# STM32_SIM800.net
KiCad netlist of a schematic drawn in Altium Designer
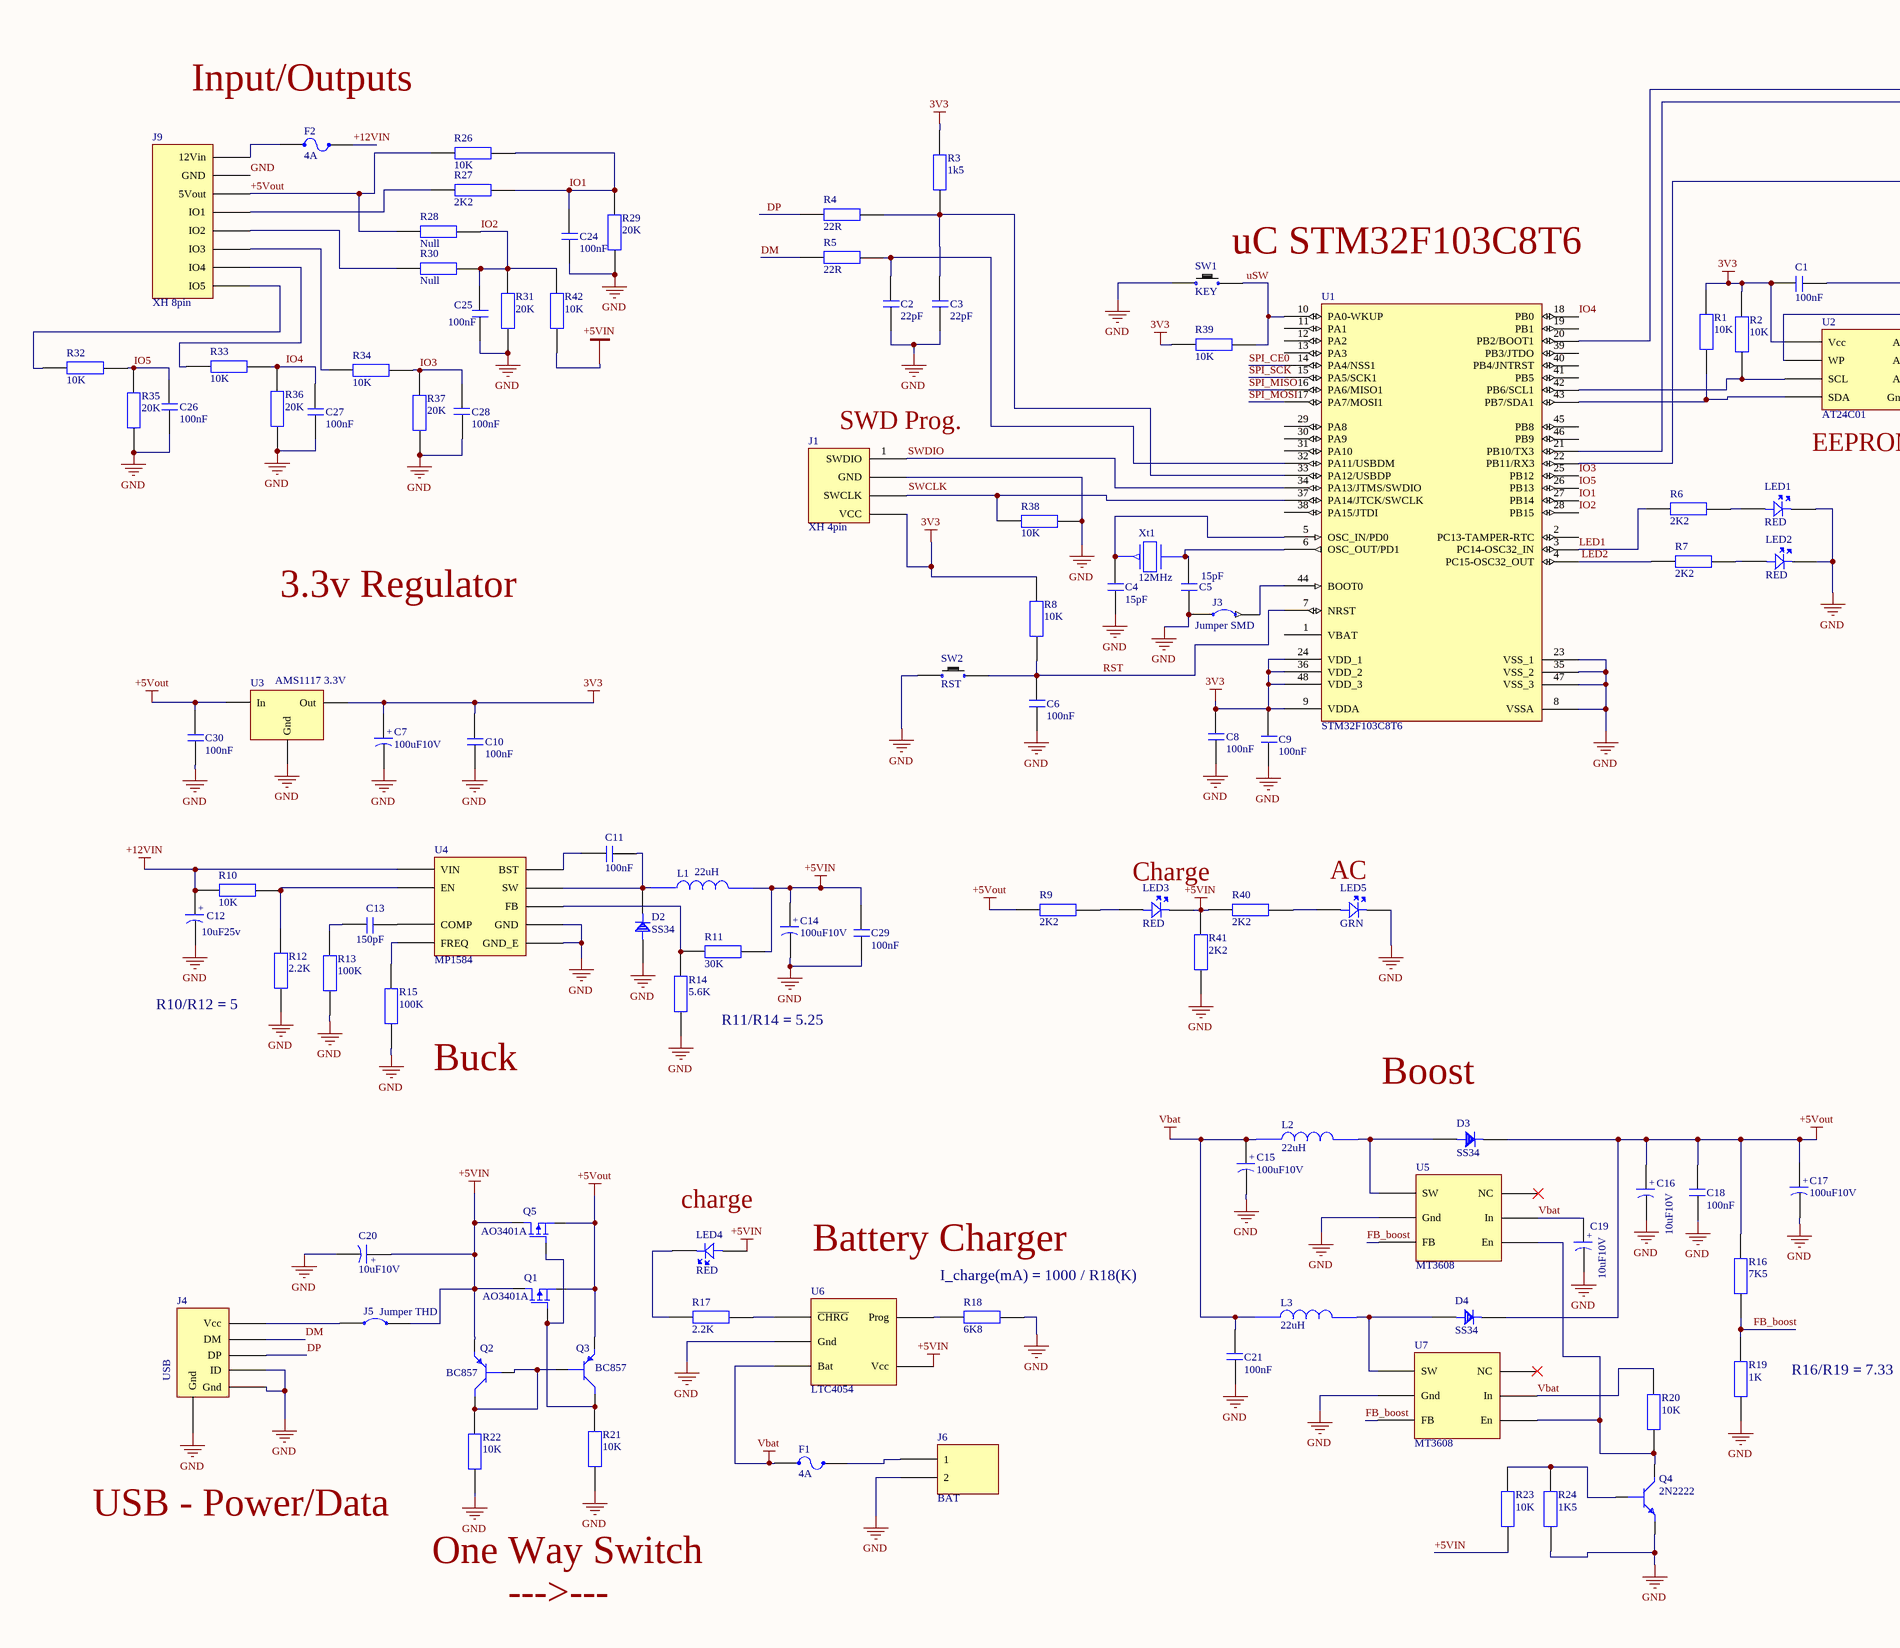
[diagram p0: STM32_SIM800.SchDoc, left]
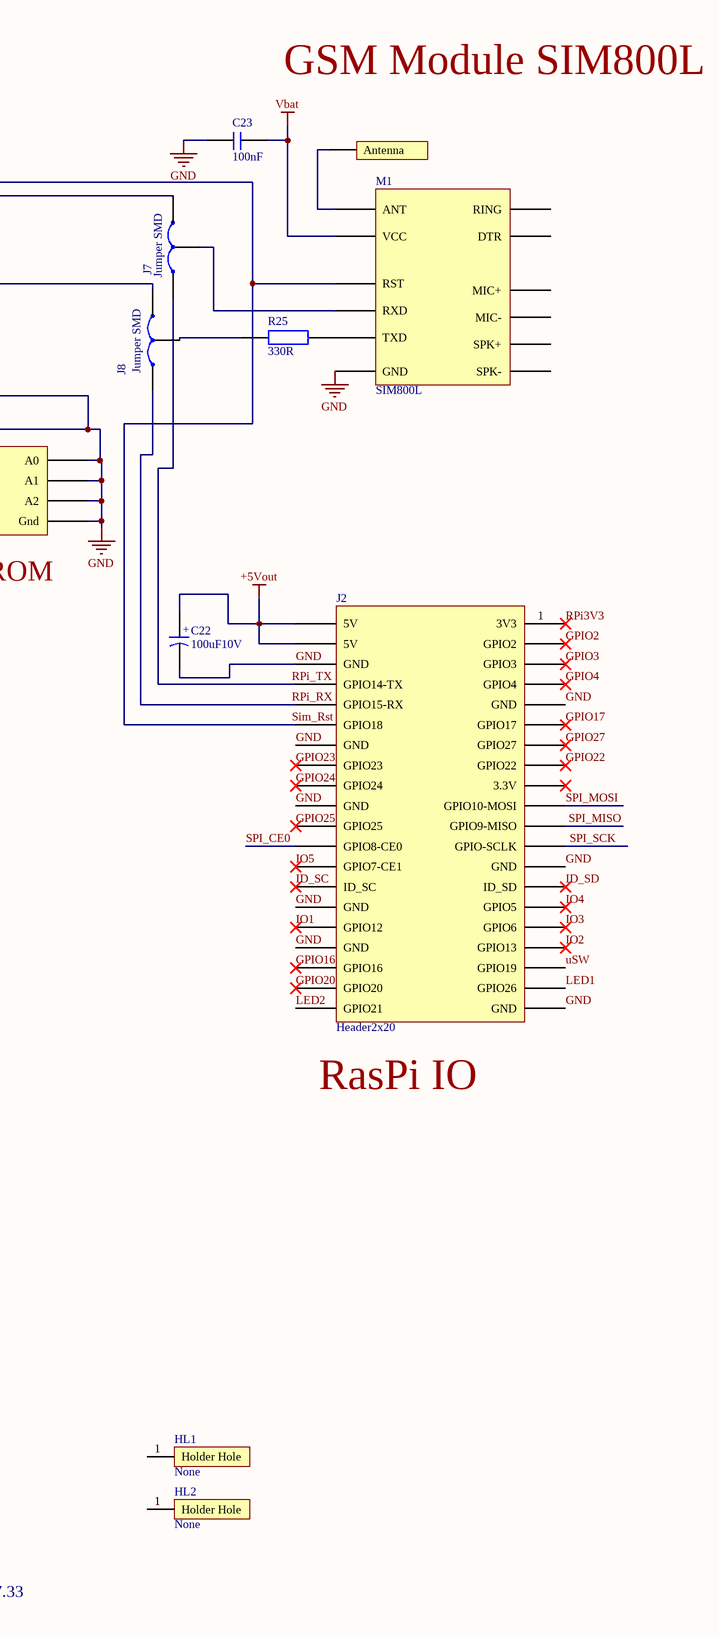
[diagram p1: STM32_SIM800.SchDoc, right]

(export (version "E")
  (design (tool "Eeschema 10.0.6"))
  (components
    (comp (ref "C1")
      (value "100nF")
      (footprint "CAP_0805")
      (description "Capacitor SMD 0805")
      (libsource (lib "My_Integrated_Library") (part "Cap0805"))
    )
    (comp (ref "C2")
      (value "22pF")
      (footprint "CAP_0805")
      (description "Capacitor SMD 0805")
      (libsource (lib "My_Integrated_Library") (part "Cap0805"))
    )
    (comp (ref "C3")
      (value "22pF")
      (footprint "CAP_0805")
      (description "Capacitor SMD 0805")
      (libsource (lib "My_Integrated_Library") (part "Cap0805"))
    )
    (comp (ref "C4")
      (value "15pF")
      (footprint "CAP_0805")
      (description "Capacitor SMD 0805")
      (libsource (lib "My_Integrated_Library") (part "Cap0805"))
    )
    (comp (ref "C5")
      (value "15pF")
      (footprint "CAP_0805")
      (description "Capacitor SMD 0805")
      (libsource (lib "My_Integrated_Library") (part "Cap0805"))
    )
    (comp (ref "C6")
      (value "100nF")
      (footprint "CAP_0805")
      (description "Capacitor SMD 0805")
      (libsource (lib "My_Integrated_Library") (part "Cap0805"))
    )
    (comp (ref "C7")
      (value "100uF10V")
      (footprint "Cap_Tan_Size_B")
      (description "Capacitor SMD Tantalium Size B")
      (libsource (lib "My_Integrated_Library") (part "Cap_Tant_B"))
    )
    (comp (ref "C8")
      (value "100nF")
      (footprint "CAP_0805")
      (description "Capacitor SMD 0805")
      (libsource (lib "My_Integrated_Library") (part "Cap0805"))
    )
    (comp (ref "C9")
      (value "100nF")
      (footprint "CAP_0805")
      (description "Capacitor SMD 0805")
      (libsource (lib "My_Integrated_Library") (part "Cap0805"))
    )
    (comp (ref "C10")
      (value "100nF")
      (footprint "CAP_0805")
      (description "Capacitor SMD 0805")
      (libsource (lib "My_Integrated_Library") (part "Cap0805"))
    )
    (comp (ref "C11")
      (value "100nF")
      (footprint "CAP_0805")
      (description "Capacitor SMD 0805")
      (libsource (lib "My_Integrated_Library") (part "Cap0805"))
    )
    (comp (ref "C12")
      (value "10uF25v")
      (footprint "Cap_Tan_Size_B")
      (description "Capacitor SMD Tantalium Size B")
      (libsource (lib "My_Integrated_Library") (part "Cap_Tant_B"))
    )
    (comp (ref "C13")
      (value "150pF")
      (footprint "CAP_0805")
      (description "Capacitor SMD 0805")
      (libsource (lib "My_Integrated_Library") (part "Cap0805"))
    )
    (comp (ref "C14")
      (value "100uF10V")
      (footprint "Cap_Tan_Size_B")
      (description "Capacitor SMD Tantalium Size B")
      (libsource (lib "My_Integrated_Library") (part "Cap_Tant_B"))
    )
    (comp (ref "C15")
      (value "100uF10V")
      (footprint "Cap_Tan_Size_B")
      (description "Capacitor SMD Tantalium Size B")
      (libsource (lib "My_Integrated_Library") (part "Cap_Tant_B"))
    )
    (comp (ref "C16")
      (value "10uF10V")
      (footprint "Cap_Tan_Size_B")
      (description "Capacitor SMD Tantalium Size B")
      (libsource (lib "My_Integrated_Library") (part "Cap_Tant_B"))
    )
    (comp (ref "C17")
      (value "100uF10V")
      (footprint "Cap_Tan_Size_B")
      (description "Capacitor SMD Tantalium Size B")
      (libsource (lib "My_Integrated_Library") (part "Cap_Tant_B"))
    )
    (comp (ref "C18")
      (value "100nF")
      (footprint "CAP_0805")
      (description "Capacitor SMD 0805")
      (libsource (lib "My_Integrated_Library") (part "Cap0805"))
    )
    (comp (ref "C19")
      (value "10uF10V")
      (footprint "Cap_Tan_Size_B")
      (description "Capacitor SMD Tantalium Size B")
      (libsource (lib "My_Integrated_Library") (part "Cap_Tant_B"))
    )
    (comp (ref "C20")
      (value "10uF10V")
      (footprint "Cap_Tan_Size_B")
      (description "Capacitor SMD Tantalium Size B")
      (libsource (lib "My_Integrated_Library") (part "Cap_Tant_B"))
    )
    (comp (ref "C21")
      (value "100nF")
      (footprint "CAP_0805")
      (description "Capacitor SMD 0805")
      (libsource (lib "My_Integrated_Library") (part "Cap0805"))
    )
    (comp (ref "C22")
      (value "100uF10V")
      (footprint "Cap_Tan_Size_B")
      (description "Capacitor SMD Tantalium Size B")
      (libsource (lib "My_Integrated_Library") (part "Cap_Tant_B"))
    )
    (comp (ref "C23")
      (value "100nF")
      (footprint "CAP_0805")
      (description "Capacitor SMD 0805")
      (libsource (lib "My_Integrated_Library") (part "Cap0805"))
    )
    (comp (ref "C24")
      (value "100nF")
      (footprint "CAP_0805")
      (description "Capacitor SMD 0805")
      (libsource (lib "My_Integrated_Library") (part "Cap0805"))
    )
    (comp (ref "C25")
      (value "100nF")
      (footprint "CAP_0805")
      (description "Capacitor SMD 0805")
      (libsource (lib "My_Integrated_Library") (part "Cap0805"))
    )
    (comp (ref "C26")
      (value "100nF")
      (footprint "CAP_0805")
      (description "Capacitor SMD 0805")
      (libsource (lib "My_Integrated_Library") (part "Cap0805"))
    )
    (comp (ref "C27")
      (value "100nF")
      (footprint "CAP_0805")
      (description "Capacitor SMD 0805")
      (libsource (lib "My_Integrated_Library") (part "Cap0805"))
    )
    (comp (ref "C28")
      (value "100nF")
      (footprint "CAP_0805")
      (description "Capacitor SMD 0805")
      (libsource (lib "My_Integrated_Library") (part "Cap0805"))
    )
    (comp (ref "C29")
      (value "100nF")
      (footprint "CAP_0805")
      (description "Capacitor SMD 0805")
      (libsource (lib "My_Integrated_Library") (part "Cap0805"))
    )
    (comp (ref "C30")
      (value "100nF")
      (footprint "CAP_0805")
      (description "Capacitor SMD 0805")
      (libsource (lib "My_Integrated_Library") (part "Cap0805"))
    )
    (comp (ref "D2")
      (value "SS34")
      (footprint "Diode_SMA")
      (description "Diode SMD Shotkey 1N5822 SS34")
      (libsource (lib "My_Integrated_Library") (part "Diode_SMA"))
    )
    (comp (ref "D3")
      (value "SS34")
      (footprint "Diode_SMA")
      (description "Diode SMD Shotkey 1N5822 SS34")
      (libsource (lib "My_Integrated_Library") (part "Diode_SMA"))
    )
    (comp (ref "D4")
      (value "SS34")
      (footprint "Diode_SMA")
      (description "Diode SMD Shotkey 1N5822 SS34")
      (libsource (lib "My_Integrated_Library") (part "Diode_SMA"))
    )
    (comp (ref "F1")
      (value "4A")
      (footprint "fuse_1206")
      (description "Fuse SMD 1206")
      (libsource (lib "My_Integrated_Library") (part "Fuse1206"))
    )
    (comp (ref "F2")
      (value "4A")
      (footprint "fuse_1206")
      (description "Fuse SMD 1206")
      (libsource (lib "My_Integrated_Library") (part "Fuse1206"))
    )
    (comp (ref "HL1")
      (value "None")
      (footprint "Holder_hole")
      (description "PCB Holder Hole")
      (libsource (lib "My_Integrated_Library") (part "Holder_Hole"))
    )
    (comp (ref "HL2")
      (value "None")
      (footprint "Holder_hole")
      (description "PCB Holder Hole")
      (libsource (lib "My_Integrated_Library") (part "Holder_Hole"))
    )
    (comp (ref "J1")
      (value "XH 4pin")
      (footprint "XH-4pin")
      (description "Connector XH Female 4-pin")
      (libsource (lib "My_Integrated_Library") (part "Con_XH_4pin"))
    )
    (comp (ref "J2")
      (value "Header2x20")
      (footprint "Header_2x20_female")
      (description "Pin Header 2x20 pitch=2.54mm")
      (libsource (lib "My_Integrated_Library") (part "Header2x20"))
    )
    (comp (ref "J3")
      (value "Jumper SMD")
      (footprint "Jumper_smd")
      (libsource (lib "My_Integrated_Library") (part "Jump_smd"))
    )
    (comp (ref "J4")
      (value "USB")
      (footprint "Micro_USB_smd")
      (description "Micro USB Female connector SMD")
      (libsource (lib "My_Integrated_Library") (part "MicroUSB_SMD"))
    )
    (comp (ref "J5")
      (value "Jumper THD")
      (footprint "Jumper_2pin")
      (description "Jumper pin header + jumper 2pin pirch=2.54mm")
      (libsource (lib "My_Integrated_Library") (part "Jumper DIP"))
    )
    (comp (ref "J6")
      (value "BAT")
      (footprint "XH-2pin")
      (description "Connector XH Female 2-pin")
      (libsource (lib "My_Integrated_Library") (part "Con_XH_2pin"))
    )
    (comp (ref "J7")
      (value "Jumper SMD")
      (footprint "Jumper_smd_3pin")
      (libsource (lib "My_Integrated_Library") (part "Jump_smd_3tap"))
    )
    (comp (ref "J8")
      (value "Jumper SMD")
      (footprint "Jumper_smd_3pin")
      (libsource (lib "My_Integrated_Library") (part "Jump_smd_3tap"))
    )
    (comp (ref "J9")
      (value "XH 8pin")
      (footprint "XH-8pin - RA")
      (description "Connector XH Female 8-pin")
      (libsource (lib "My_Integrated_Library") (part "Con_XH_8pin"))
    )
    (comp (ref "L1")
      (value "22uH")
      (footprint "L_10x10")
      (description "SMD Power Inductor 10X10mm")
      (libsource (lib "My_Integrated_Library") (part "Inductor_10x10"))
    )
    (comp (ref "L2")
      (value "22uH")
      (footprint "L_10x10")
      (description "SMD Power Inductor 10X10mm")
      (libsource (lib "My_Integrated_Library") (part "Inductor_10x10"))
    )
    (comp (ref "L3")
      (value "22uH")
      (footprint "L_10x10")
      (description "SMD Power Inductor 10X10mm")
      (libsource (lib "My_Integrated_Library") (part "Inductor_10x10"))
    )
    (comp (ref "LED1")
      (value "RED")
      (footprint "LED_0805_Red")
      (description "LED SMD 0805 Red")
      (libsource (lib "My_Integrated_Library") (part "LED_0805_Red"))
    )
    (comp (ref "LED2")
      (value "RED")
      (footprint "LED_0805_Red")
      (description "LED SMD 0805 Red")
      (libsource (lib "My_Integrated_Library") (part "LED_0805_Red"))
    )
    (comp (ref "LED3")
      (value "RED")
      (footprint "LED_0805_Red")
      (description "LED SMD 0805 Red")
      (libsource (lib "My_Integrated_Library") (part "LED_0805_Red"))
    )
    (comp (ref "LED4")
      (value "RED")
      (footprint "LED_0805_Red")
      (description "LED SMD 0805 Red")
      (libsource (lib "My_Integrated_Library") (part "LED_0805_Red"))
    )
    (comp (ref "LED5")
      (value "GRN")
      (footprint "LED_0805_Red")
      (description "LED SMD 0805 Red")
      (libsource (lib "My_Integrated_Library") (part "LED_0805_Red"))
    )
    (comp (ref "M1")
      (value "SIM800L")
      (footprint "SIM800L")
      (description "SIM800L GSM Module")
      (libsource (lib "My_Integrated_Library") (part "SIM800L"))
    )
    (comp (ref "Q1")
      (value "AO3401A")
      (footprint "SOT23 - P-Channel")
      (description "MOSFET P-Channel SMD SOT23")
      (libsource (lib "My_Integrated_Library") (part "Mosfet_P_SOT23"))
    )
    (comp (ref "Q2")
      (value "BC857")
      (footprint "SOT23-PNP")
      (description "PNP Transistor SMD SOT23")
      (libsource (lib "My_Integrated_Library") (part "BJT PNP SOT23"))
    )
    (comp (ref "Q3")
      (value "BC857")
      (footprint "SOT23-PNP")
      (description "PNP Transistor SMD SOT23")
      (libsource (lib "My_Integrated_Library") (part "BJT PNP SOT23"))
    )
    (comp (ref "Q4")
      (value "2N2222")
      (footprint "SOT23-NPN")
      (description "NPN Transistor SMD SOT23")
      (libsource (lib "My_Integrated_Library") (part "BJT_NPN_SOT23"))
    )
    (comp (ref "Q5")
      (value "AO3401A")
      (footprint "SOT23 - P-Channel")
      (description "MOSFET P-Channel SMD SOT23")
      (libsource (lib "My_Integrated_Library") (part "Mosfet_P_SOT23"))
    )
    (comp (ref "R1")
      (value "10K")
      (footprint "RES_0805")
      (description "Resistor SMD 0805")
      (libsource (lib "My_Integrated_Library") (part "Res0805"))
    )
    (comp (ref "R2")
      (value "10K")
      (footprint "RES_0805")
      (description "Resistor SMD 0805")
      (libsource (lib "My_Integrated_Library") (part "Res0805"))
    )
    (comp (ref "R3")
      (value "1k5")
      (footprint "RES_0805")
      (description "Resistor SMD 0805")
      (libsource (lib "My_Integrated_Library") (part "Res0805"))
    )
    (comp (ref "R4")
      (value "22R")
      (footprint "RES_0805")
      (description "Resistor SMD 0805")
      (libsource (lib "My_Integrated_Library") (part "Res0805"))
    )
    (comp (ref "R5")
      (value "22R")
      (footprint "RES_0805")
      (description "Resistor SMD 0805")
      (libsource (lib "My_Integrated_Library") (part "Res0805"))
    )
    (comp (ref "R6")
      (value "2K2")
      (footprint "RES_0805")
      (description "Resistor SMD 0805")
      (libsource (lib "My_Integrated_Library") (part "Res0805"))
    )
    (comp (ref "R7")
      (value "2K2")
      (footprint "RES_0805")
      (description "Resistor SMD 0805")
      (libsource (lib "My_Integrated_Library") (part "Res0805"))
    )
    (comp (ref "R8")
      (value "10K")
      (footprint "RES_0805")
      (description "Resistor SMD 0805")
      (libsource (lib "My_Integrated_Library") (part "Res0805"))
    )
    (comp (ref "R9")
      (value "2K2")
      (footprint "RES_0805")
      (description "Resistor SMD 0805")
      (libsource (lib "My_Integrated_Library") (part "Res0805"))
    )
    (comp (ref "R10")
      (value "10K")
      (footprint "RES_0805")
      (description "Resistor SMD 0805")
      (libsource (lib "My_Integrated_Library") (part "Res0805"))
    )
    (comp (ref "R11")
      (value "30K")
      (footprint "RES_0805")
      (description "Resistor SMD 0805")
      (libsource (lib "My_Integrated_Library") (part "Res0805"))
    )
    (comp (ref "R12")
      (value "2.2K")
      (footprint "RES_0805")
      (description "Resistor SMD 0805")
      (libsource (lib "My_Integrated_Library") (part "Res0805"))
    )
    (comp (ref "R13")
      (value "100K")
      (footprint "RES_0805")
      (description "Resistor SMD 0805")
      (libsource (lib "My_Integrated_Library") (part "Res0805"))
    )
    (comp (ref "R14")
      (value "5.6K")
      (footprint "RES_0805")
      (description "Resistor SMD 0805")
      (libsource (lib "My_Integrated_Library") (part "Res0805"))
    )
    (comp (ref "R15")
      (value "100K")
      (footprint "RES_0805")
      (description "Resistor SMD 0805")
      (libsource (lib "My_Integrated_Library") (part "Res0805"))
    )
    (comp (ref "R16")
      (value "7K5")
      (footprint "RES_0805")
      (description "Resistor SMD 0805")
      (libsource (lib "My_Integrated_Library") (part "Res0805"))
    )
    (comp (ref "R17")
      (value "2.2K")
      (footprint "RES_0805")
      (description "Resistor SMD 0805")
      (libsource (lib "My_Integrated_Library") (part "Res0805"))
    )
    (comp (ref "R18")
      (value "6K8")
      (footprint "RES_0805")
      (description "Resistor SMD 0805")
      (libsource (lib "My_Integrated_Library") (part "Res0805"))
    )
    (comp (ref "R19")
      (value "1K")
      (footprint "RES_0805")
      (description "Resistor SMD 0805")
      (libsource (lib "My_Integrated_Library") (part "Res0805"))
    )
    (comp (ref "R20")
      (value "10K")
      (footprint "RES_0805")
      (description "Resistor SMD 0805")
      (libsource (lib "My_Integrated_Library") (part "Res0805"))
    )
    (comp (ref "R21")
      (value "10K")
      (footprint "RES_0805")
      (description "Resistor SMD 0805")
      (libsource (lib "My_Integrated_Library") (part "Res0805"))
    )
    (comp (ref "R22")
      (value "10K")
      (footprint "RES_0805")
      (description "Resistor SMD 0805")
      (libsource (lib "My_Integrated_Library") (part "Res0805"))
    )
    (comp (ref "R23")
      (value "10K")
      (footprint "RES_0805")
      (description "Resistor SMD 0805")
      (libsource (lib "My_Integrated_Library") (part "Res0805"))
    )
    (comp (ref "R24")
      (value "1K5")
      (footprint "RES_0805")
      (description "Resistor SMD 0805")
      (libsource (lib "My_Integrated_Library") (part "Res0805"))
    )
    (comp (ref "R25")
      (value "330R")
      (footprint "RES_0805")
      (description "Resistor SMD 0805")
      (libsource (lib "My_Integrated_Library") (part "Res0805"))
    )
    (comp (ref "R26")
      (value "10K")
      (footprint "RES_0805")
      (description "Resistor SMD 0805")
      (libsource (lib "My_Integrated_Library") (part "Res0805"))
    )
    (comp (ref "R27")
      (value "2K2")
      (footprint "RES_0805")
      (description "Resistor SMD 0805")
      (libsource (lib "My_Integrated_Library") (part "Res0805"))
    )
    (comp (ref "R28")
      (value "Null")
      (footprint "RES_0805")
      (description "Resistor SMD 0805")
      (libsource (lib "My_Integrated_Library") (part "Res0805"))
    )
    (comp (ref "R29")
      (value "20K")
      (footprint "RES_0805")
      (description "Resistor SMD 0805")
      (libsource (lib "My_Integrated_Library") (part "Res0805"))
    )
    (comp (ref "R30")
      (value "Null")
      (footprint "RES_0805")
      (description "Resistor SMD 0805")
      (libsource (lib "My_Integrated_Library") (part "Res0805"))
    )
    (comp (ref "R31")
      (value "20K")
      (footprint "RES_0805")
      (description "Resistor SMD 0805")
      (libsource (lib "My_Integrated_Library") (part "Res0805"))
    )
    (comp (ref "R32")
      (value "10K")
      (footprint "RES_0805")
      (description "Resistor SMD 0805")
      (libsource (lib "My_Integrated_Library") (part "Res0805"))
    )
    (comp (ref "R33")
      (value "10K")
      (footprint "RES_0805")
      (description "Resistor SMD 0805")
      (libsource (lib "My_Integrated_Library") (part "Res0805"))
    )
    (comp (ref "R34")
      (value "10K")
      (footprint "RES_0805")
      (description "Resistor SMD 0805")
      (libsource (lib "My_Integrated_Library") (part "Res0805"))
    )
    (comp (ref "R35")
      (value "20K")
      (footprint "RES_0805")
      (description "Resistor SMD 0805")
      (libsource (lib "My_Integrated_Library") (part "Res0805"))
    )
    (comp (ref "R36")
      (value "20K")
      (footprint "RES_0805")
      (description "Resistor SMD 0805")
      (libsource (lib "My_Integrated_Library") (part "Res0805"))
    )
    (comp (ref "R37")
      (value "20K")
      (footprint "RES_0805")
      (description "Resistor SMD 0805")
      (libsource (lib "My_Integrated_Library") (part "Res0805"))
    )
    (comp (ref "R38")
      (value "10K")
      (footprint "RES_0805")
      (description "Resistor SMD 0805")
      (libsource (lib "My_Integrated_Library") (part "Res0805"))
    )
    (comp (ref "R39")
      (value "10K")
      (footprint "RES_0805")
      (description "Resistor SMD 0805")
      (libsource (lib "My_Integrated_Library") (part "Res0805"))
    )
    (comp (ref "R40")
      (value "2K2")
      (footprint "RES_0805")
      (description "Resistor SMD 0805")
      (libsource (lib "My_Integrated_Library") (part "Res0805"))
    )
    (comp (ref "R41")
      (value "2K2")
      (footprint "RES_0805")
      (description "Resistor SMD 0805")
      (libsource (lib "My_Integrated_Library") (part "Res0805"))
    )
    (comp (ref "R42")
      (value "10K")
      (footprint "RES_0805")
      (description "Resistor SMD 0805")
      (libsource (lib "My_Integrated_Library") (part "Res0805"))
    )
    (comp (ref "SW1")
      (value "KEY")
      (footprint "Tact_SW_SMD")
      (description "Tact switch SMD 2pin")
      (libsource (lib "My_Integrated_Library") (part "Tact_sw"))
    )
    (comp (ref "SW2")
      (value "RST")
      (footprint "Tact_SW_SMD")
      (description "Tact switch SMD 2pin")
      (libsource (lib "My_Integrated_Library") (part "Tact_sw"))
    )
    (comp (ref "TP1")
      (value "Ant.")
      (footprint "TP")
      (description "Test point")
      (libsource (lib "My_Integrated_Library") (part "TP"))
    )
    (comp (ref "U1")
      (value "STM32F103C8T6")
      (footprint "STM32F103C8-LQFP-48")
      (description "STM32 ARM-based 32-bit MCU with 64 Kbytes Flash, 48-pin LQFP, Industrial Temperature")
      (fields (field (name "PUBLISHER") "Altium Limited"))
      (libsource (lib "My_Integrated_Library") (part "STM32F103C8T6"))
    )
    (comp (ref "U2")
      (value "AT24C01")
      (footprint "AT24C01_SOP8")
      (description "AT24C01 EEPROM SMD SO8")
      (libsource (lib "My_Integrated_Library") (part "AT24C01"))
    )
    (comp (ref "U3")
      (value "AMS1117 3.3V")
      (footprint "AMS1117-SOT223")
      (description "AMS1117 Regulator 3.3V SMD SOT223")
      (libsource (lib "My_Integrated_Library") (part "AMS1117-SOT223"))
    )
    (comp (ref "U4")
      (value "MP1584")
      (footprint "MP1584-SOP8")
      (description "BUCK SMD SO8")
      (libsource (lib "My_Integrated_Library") (part "MP1584"))
    )
    (comp (ref "U5")
      (value "MT3608")
      (footprint "MT3608_SOT23-6")
      (description "Boost switching")
      (libsource (lib "My_Integrated_Library") (part "MT3608"))
    )
    (comp (ref "U6")
      (value "LTC4054")
      (footprint "LTC4054-4.2_SOT23-5")
      (description "Li-Ion Battery charger")
      (libsource (lib "My_Integrated_Library") (part "LTC4054-4.2"))
    )
    (comp (ref "U7")
      (value "MT3608")
      (footprint "MT3608_SOT23-6")
      (description "Boost switching")
      (libsource (lib "My_Integrated_Library") (part "MT3608"))
    )
    (comp (ref "Xt1")
      (value "12MHz")
      (footprint "Xtal_SMD")
      (description "Crystal Oscillator SMD")
      (libsource (lib "My_Integrated_Library") (part "Xtal_SMD"))
    )
  )
  (nets
    (net (code "1") (name "+5VIN") (class "Default")
      (node (ref "C14") (pin "+") (pinfunction "+_+") (pintype "passive"))
      (node (ref "C20") (pin "+") (pinfunction "+_+") (pintype "passive"))
      (node (ref "C29") (pin "2") (pinfunction "2_2") (pintype "passive"))
      (node (ref "J5") (pin "1") (pinfunction "1_1") (pintype "passive"))
      (node (ref "L1") (pin "2") (pinfunction "2_2") (pintype "passive"))
      (node (ref "LED3") (pin "2") (pinfunction "2_2") (pintype "passive"))
      (node (ref "LED4") (pin "1") (pinfunction "1_1") (pintype "passive"))
      (node (ref "Q1") (pin "D") (pinfunction "D_D") (pintype "passive"))
      (node (ref "Q2") (pin "E") (pinfunction "E_E") (pintype "passive"))
      (node (ref "Q5") (pin "D") (pinfunction "D_D") (pintype "passive"))
      (node (ref "R11") (pin "1") (pinfunction "1_1") (pintype "passive"))
      (node (ref "R23") (pin "2") (pinfunction "2_2") (pintype "passive"))
      (node (ref "R40") (pin "2") (pinfunction "2_2") (pintype "passive"))
      (node (ref "R41") (pin "1") (pinfunction "1_1") (pintype "passive"))
      (node (ref "R42") (pin "2") (pinfunction "2_2") (pintype "passive"))
      (node (ref "U6") (pin "VCC") (pinfunction "Vcc_VCC") (pintype "passive"))
    )
    (net (code "2") (name "+5Vout") (class "Default")
      (node (ref "C16") (pin "+") (pinfunction "+_+") (pintype "passive"))
      (node (ref "C17") (pin "+") (pinfunction "+_+") (pintype "passive"))
      (node (ref "C18") (pin "1") (pinfunction "1_1") (pintype "passive"))
      (node (ref "C22") (pin "+") (pinfunction "+_+") (pintype "passive"))
      (node (ref "C30") (pin "2") (pinfunction "2_2") (pintype "passive"))
      (node (ref "D3") (pin "K") (pinfunction "K_K") (pintype "passive"))
      (node (ref "D4") (pin "K") (pinfunction "K_K") (pintype "passive"))
      (node (ref "J2") (pin "2") (pinfunction "5V_2") (pintype "passive"))
      (node (ref "J2") (pin "4") (pinfunction "5V_4") (pintype "passive"))
      (node (ref "J9") (pin "3") (pinfunction "5Vout_3") (pintype "passive"))
      (node (ref "Q1") (pin "S") (pinfunction "S_S") (pintype "passive"))
      (node (ref "Q3") (pin "E") (pinfunction "E_E") (pintype "passive"))
      (node (ref "Q5") (pin "S") (pinfunction "S_S") (pintype "passive"))
      (node (ref "R16") (pin "2") (pinfunction "2_2") (pintype "passive"))
      (node (ref "R26") (pin "1") (pinfunction "1_1") (pintype "passive"))
      (node (ref "R28") (pin "1") (pinfunction "1_1") (pintype "passive"))
      (node (ref "R9") (pin "2") (pinfunction "2_2") (pintype "passive"))
      (node (ref "U3") (pin "1") (pinfunction "In_1") (pintype "passive"))
    )
    (net (code "3") (name "+12VIN") (class "Default")
      (node (ref "C12") (pin "+") (pinfunction "+_+") (pintype "passive"))
      (node (ref "F2") (pin "1") (pinfunction "1_1") (pintype "passive"))
      (node (ref "R10") (pin "1") (pinfunction "1_1") (pintype "passive"))
      (node (ref "U4") (pin "VIN") (pinfunction "VIN_VIN") (pintype "passive"))
    )
    (net (code "4") (name "/DM") (class "Default")
      (node (ref "J4") (pin "2") (pinfunction "DM_2") (pintype "passive"))
      (node (ref "R5") (pin "2") (pinfunction "2_2") (pintype "passive"))
    )
    (net (code "5") (name "/DP") (class "Default")
      (node (ref "J4") (pin "3") (pinfunction "DP_3") (pintype "passive"))
      (node (ref "R4") (pin "2") (pinfunction "2_2") (pintype "passive"))
    )
    (net (code "6") (name "/FB_boost") (class "Default")
      (node (ref "R16") (pin "1") (pinfunction "1_1") (pintype "passive"))
      (node (ref "R19") (pin "2") (pinfunction "2_2") (pintype "passive"))
      (node (ref "U5") (pin "FB") (pinfunction "FB_FB") (pintype "passive"))
      (node (ref "U7") (pin "FB") (pinfunction "FB_FB") (pintype "passive"))
    )
    (net (code "7") (name "/GPIO2") (class "Default")
      (node (ref "J2") (pin "3") (pinfunction "GPIO2_3") (pintype "passive+no_connect"))
    )
    (net (code "8") (name "/GPIO3") (class "Default")
      (node (ref "J2") (pin "5") (pinfunction "GPIO3_5") (pintype "passive+no_connect"))
    )
    (net (code "9") (name "/GPIO4") (class "Default")
      (node (ref "J2") (pin "7") (pinfunction "GPIO4_7") (pintype "passive+no_connect"))
    )
    (net (code "10") (name "/GPIO16") (class "Default")
      (node (ref "J2") (pin "36") (pinfunction "GPIO16_36") (pintype "passive+no_connect"))
    )
    (net (code "11") (name "/GPIO17") (class "Default")
      (node (ref "J2") (pin "11") (pinfunction "GPIO17_11") (pintype "passive+no_connect"))
    )
    (net (code "12") (name "/GPIO20") (class "Default")
      (node (ref "J2") (pin "38") (pinfunction "GPIO20_38") (pintype "passive+no_connect"))
    )
    (net (code "13") (name "/GPIO22") (class "Default")
      (node (ref "J2") (pin "15") (pinfunction "GPIO22_15") (pintype "passive+no_connect"))
    )
    (net (code "14") (name "/GPIO23") (class "Default")
      (node (ref "J2") (pin "16") (pinfunction "GPIO23_16") (pintype "passive+no_connect"))
    )
    (net (code "15") (name "/GPIO24") (class "Default")
      (node (ref "J2") (pin "18") (pinfunction "GPIO24_18") (pintype "passive+no_connect"))
    )
    (net (code "16") (name "/GPIO25") (class "Default")
      (node (ref "J2") (pin "22") (pinfunction "GPIO25_22") (pintype "passive+no_connect"))
    )
    (net (code "17") (name "/GPIO27") (class "Default")
      (node (ref "J2") (pin "13") (pinfunction "GPIO27_13") (pintype "passive+no_connect"))
    )
    (net (code "18") (name "/ID_SC") (class "Default")
      (node (ref "J2") (pin "28") (pinfunction "ID_SC_28") (pintype "passive+no_connect"))
    )
    (net (code "19") (name "/ID_SD") (class "Default")
      (node (ref "J2") (pin "27") (pinfunction "ID_SD_27") (pintype "passive+no_connect"))
    )
    (net (code "20") (name "/IO1") (class "Default")
      (node (ref "C24") (pin "2") (pinfunction "2_2") (pintype "passive"))
      (node (ref "J2") (pin "32") (pinfunction "GPIO12_32") (pintype "passive"))
      (node (ref "R26") (pin "2") (pinfunction "2_2") (pintype "passive"))
      (node (ref "R27") (pin "1") (pinfunction "1_1") (pintype "passive"))
      (node (ref "R29") (pin "1") (pinfunction "1_1") (pintype "passive"))
      (node (ref "U1") (pin "27") (pinfunction "PB14_27") (pintype "bidirectional"))
    )
    (net (code "21") (name "/IO2") (class "Default")
      (node (ref "C25") (pin "2") (pinfunction "2_2") (pintype "passive"))
      (node (ref "J2") (pin "33") (pinfunction "GPIO13_33") (pintype "passive"))
      (node (ref "R28") (pin "2") (pinfunction "2_2") (pintype "passive"))
      (node (ref "R30") (pin "1") (pinfunction "1_1") (pintype "passive"))
      (node (ref "R31") (pin "1") (pinfunction "1_1") (pintype "passive"))
      (node (ref "R42") (pin "1") (pinfunction "1_1") (pintype "passive"))
      (node (ref "U1") (pin "28") (pinfunction "PB15_28") (pintype "bidirectional"))
    )
    (net (code "22") (name "/IO3") (class "Default")
      (node (ref "C28") (pin "1") (pinfunction "1_1") (pintype "passive"))
      (node (ref "J2") (pin "31") (pinfunction "GPIO6_31") (pintype "passive"))
      (node (ref "R34") (pin "1") (pinfunction "1_1") (pintype "passive"))
      (node (ref "R37") (pin "1") (pinfunction "1_1") (pintype "passive"))
      (node (ref "U1") (pin "25") (pinfunction "PB12_25") (pintype "bidirectional"))
    )
    (net (code "23") (name "/IO4") (class "Default")
      (node (ref "C27") (pin "2") (pinfunction "2_2") (pintype "passive"))
      (node (ref "J2") (pin "29") (pinfunction "GPIO5_29") (pintype "passive"))
      (node (ref "R33") (pin "1") (pinfunction "1_1") (pintype "passive"))
      (node (ref "R36") (pin "1") (pinfunction "1_1") (pintype "passive"))
      (node (ref "U1") (pin "18") (pinfunction "PB0_18") (pintype "bidirectional"))
    )
    (net (code "24") (name "/IO5") (class "Default")
      (node (ref "C26") (pin "2") (pinfunction "2_2") (pintype "passive"))
      (node (ref "J2") (pin "26") (pinfunction "GPIO7-CE1_26") (pintype "passive"))
      (node (ref "R32") (pin "1") (pinfunction "1_1") (pintype "passive"))
      (node (ref "R35") (pin "1") (pinfunction "1_1") (pintype "passive"))
      (node (ref "U1") (pin "26") (pinfunction "PB13_26") (pintype "bidirectional"))
    )
    (net (code "25") (name "/LED1") (class "Default")
      (node (ref "J2") (pin "37") (pinfunction "GPIO26_37") (pintype "passive"))
      (node (ref "R6") (pin "1") (pinfunction "1_1") (pintype "passive"))
      (node (ref "U1") (pin "3") (pinfunction "PC14-OSC32_IN_3") (pintype "bidirectional"))
    )
    (net (code "26") (name "/LED2") (class "Default")
      (node (ref "J2") (pin "40") (pinfunction "GPIO21_40") (pintype "passive"))
      (node (ref "R7") (pin "1") (pinfunction "1_1") (pintype "passive"))
      (node (ref "U1") (pin "4") (pinfunction "PC15-OSC32_OUT_4") (pintype "bidirectional"))
    )
    (net (code "27") (name "/RPi3V3") (class "Default")
      (node (ref "J2") (pin "1") (pinfunction "3V3_1") (pintype "passive+no_connect"))
    )
    (net (code "28") (name "/RPi_RX") (class "Default")
      (node (ref "J2") (pin "10") (pinfunction "GPIO15-RX_10") (pintype "passive"))
      (node (ref "J8") (pin "1") (pinfunction "1_1") (pintype "passive"))
    )
    (net (code "29") (name "/RPi_TX") (class "Default")
      (node (ref "J2") (pin "8") (pinfunction "GPIO14-TX_8") (pintype "passive"))
      (node (ref "J7") (pin "1") (pinfunction "1_1") (pintype "passive"))
    )
    (net (code "30") (name "/RST") (class "Default")
      (node (ref "C6") (pin "2") (pinfunction "2_2") (pintype "passive"))
      (node (ref "R8") (pin "1") (pinfunction "1_1") (pintype "passive"))
      (node (ref "SW2") (pin "1") (pinfunction "1_1") (pintype "passive"))
      (node (ref "U1") (pin "7") (pinfunction "NRST_7") (pintype "bidirectional"))
    )
    (net (code "31") (name "/SPI_CE0") (class "Default")
      (node (ref "J2") (pin "24") (pinfunction "GPIO8-CE0_24") (pintype "passive"))
      (node (ref "U1") (pin "14") (pinfunction "PA4/NSS1_14") (pintype "bidirectional"))
    )
    (net (code "32") (name "/SPI_MISO") (class "Default")
      (node (ref "J2") (pin "21") (pinfunction "GPIO9-MISO_21") (pintype "passive"))
      (node (ref "U1") (pin "16") (pinfunction "PA6/MISO1_16") (pintype "bidirectional"))
    )
    (net (code "33") (name "/SPI_MOSI") (class "Default")
      (node (ref "J2") (pin "19") (pinfunction "GPIO10-MOSI_19") (pintype "passive"))
      (node (ref "U1") (pin "17") (pinfunction "PA7/MOSI1_17") (pintype "bidirectional"))
    )
    (net (code "34") (name "/SPI_SCK") (class "Default")
      (node (ref "J2") (pin "23") (pinfunction "GPIO-SCLK_23") (pintype "passive"))
      (node (ref "U1") (pin "15") (pinfunction "PA5/SCK1_15") (pintype "bidirectional"))
    )
    (net (code "36") (name "/SWDIO") (class "Default")
      (node (ref "J1") (pin "1") (pinfunction "SWDIO_1") (pintype "passive"))
      (node (ref "U1") (pin "34") (pinfunction "PA13/JTMS/SWDIO_34") (pintype "bidirectional"))
    )
    (net (code "37") (name "/Sim_Rst") (class "Default")
      (node (ref "J2") (pin "12") (pinfunction "GPIO18_12") (pintype "passive"))
      (node (ref "M1") (pin "RST") (pinfunction "RST_RST") (pintype "passive"))
      (node (ref "U1") (pin "20") (pinfunction "PB2/BOOT1_20") (pintype "bidirectional"))
    )
    (net (code "38") (name "/uSW") (class "Default")
      (node (ref "J2") (pin "35") (pinfunction "GPIO19_35") (pintype "passive"))
      (node (ref "R39") (pin "2") (pinfunction "2_2") (pintype "passive"))
      (node (ref "SW1") (pin "2") (pinfunction "2_2") (pintype "passive"))
      (node (ref "U1") (pin "10") (pinfunction "PA0-WKUP_10") (pintype "bidirectional"))
    )
    (net (code "39") (name "3V3") (class "Default")
      (node (ref "C1") (pin "1") (pinfunction "1_1") (pintype "passive"))
      (node (ref "C10") (pin "2") (pinfunction "2_2") (pintype "passive"))
      (node (ref "C7") (pin "+") (pinfunction "+_+") (pintype "passive"))
      (node (ref "C8") (pin "2") (pinfunction "2_2") (pintype "passive"))
      (node (ref "C9") (pin "2") (pinfunction "2_2") (pintype "passive"))
      (node (ref "J1") (pin "4") (pinfunction "VCC_4") (pintype "passive"))
      (node (ref "R1") (pin "2") (pinfunction "2_2") (pintype "passive"))
      (node (ref "R2") (pin "2") (pinfunction "2_2") (pintype "passive"))
      (node (ref "R3") (pin "2") (pinfunction "2_2") (pintype "passive"))
      (node (ref "R39") (pin "1") (pinfunction "1_1") (pintype "passive"))
      (node (ref "R8") (pin "2") (pinfunction "2_2") (pintype "passive"))
      (node (ref "U1") (pin "24") (pinfunction "VDD_1_24") (pintype "power_in"))
      (node (ref "U1") (pin "36") (pinfunction "VDD_2_36") (pintype "power_in"))
      (node (ref "U1") (pin "48") (pinfunction "VDD_3_48") (pintype "power_in"))
      (node (ref "U1") (pin "9") (pinfunction "VDDA_9") (pintype "power_in"))
      (node (ref "U2") (pin "8") (pinfunction "Vcc_8") (pintype "passive"))
      (node (ref "U3") (pin "3") (pinfunction "Out_3") (pintype "passive"))
    )
    (net (code "40") (name "GND") (class "Default")
      (node (ref "C1") (pin "2") (pinfunction "2_2") (pintype "passive"))
      (node (ref "C10") (pin "1") (pinfunction "1_1") (pintype "passive"))
      (node (ref "C12") (pin "-") (pinfunction "-_-") (pintype "passive"))
      (node (ref "C14") (pin "-") (pinfunction "-_-") (pintype "passive"))
      (node (ref "C15") (pin "-") (pinfunction "-_-") (pintype "passive"))
      (node (ref "C16") (pin "-") (pinfunction "-_-") (pintype "passive"))
      (node (ref "C17") (pin "-") (pinfunction "-_-") (pintype "passive"))
      (node (ref "C18") (pin "2") (pinfunction "2_2") (pintype "passive"))
      (node (ref "C19") (pin "-") (pinfunction "-_-") (pintype "passive"))
      (node (ref "C2") (pin "1") (pinfunction "1_1") (pintype "passive"))
      (node (ref "C20") (pin "-") (pinfunction "-_-") (pintype "passive"))
      (node (ref "C21") (pin "2") (pinfunction "2_2") (pintype "passive"))
      (node (ref "C22") (pin "-") (pinfunction "-_-") (pintype "passive"))
      (node (ref "C23") (pin "1") (pinfunction "1_1") (pintype "passive"))
      (node (ref "C24") (pin "1") (pinfunction "1_1") (pintype "passive"))
      (node (ref "C25") (pin "1") (pinfunction "1_1") (pintype "passive"))
      (node (ref "C26") (pin "1") (pinfunction "1_1") (pintype "passive"))
      (node (ref "C27") (pin "1") (pinfunction "1_1") (pintype "passive"))
      (node (ref "C28") (pin "2") (pinfunction "2_2") (pintype "passive"))
      (node (ref "C29") (pin "1") (pinfunction "1_1") (pintype "passive"))
      (node (ref "C3") (pin "1") (pinfunction "1_1") (pintype "passive"))
      (node (ref "C30") (pin "1") (pinfunction "1_1") (pintype "passive"))
      (node (ref "C4") (pin "1") (pinfunction "1_1") (pintype "passive"))
      (node (ref "C5") (pin "1") (pinfunction "1_1") (pintype "passive"))
      (node (ref "C6") (pin "1") (pinfunction "1_1") (pintype "passive"))
      (node (ref "C7") (pin "-") (pinfunction "-_-") (pintype "passive"))
      (node (ref "C8") (pin "1") (pinfunction "1_1") (pintype "passive"))
      (node (ref "C9") (pin "1") (pinfunction "1_1") (pintype "passive"))
      (node (ref "D2") (pin "A") (pinfunction "A_A") (pintype "passive"))
      (node (ref "J1") (pin "2") (pinfunction "GND_2") (pintype "passive"))
      (node (ref "J2") (pin "14") (pinfunction "GND_14") (pintype "passive"))
      (node (ref "J2") (pin "20") (pinfunction "GND_20") (pintype "passive"))
      (node (ref "J2") (pin "25") (pinfunction "GND_25") (pintype "passive"))
      (node (ref "J2") (pin "30") (pinfunction "GND_30") (pintype "passive"))
      (node (ref "J2") (pin "34") (pinfunction "GND_34") (pintype "passive"))
      (node (ref "J2") (pin "39") (pinfunction "GND_39") (pintype "passive"))
      (node (ref "J2") (pin "6") (pinfunction "GND_6") (pintype "passive"))
      (node (ref "J2") (pin "9") (pinfunction "GND_9") (pintype "passive"))
      (node (ref "J3") (pin "2") (pinfunction "2_2") (pintype "passive"))
      (node (ref "J4") (pin "4") (pinfunction "ID_4") (pintype "passive"))
      (node (ref "J4") (pin "5") (pinfunction "Gnd_5") (pintype "passive"))
      (node (ref "J4") (pin "6") (pinfunction "Gnd_6") (pintype "passive"))
      (node (ref "J6") (pin "2") (pinfunction "2_2") (pintype "passive"))
      (node (ref "J9") (pin "2") (pinfunction "GND_2") (pintype "passive"))
      (node (ref "LED1") (pin "2") (pinfunction "2_2") (pintype "passive"))
      (node (ref "LED2") (pin "2") (pinfunction "2_2") (pintype "passive"))
      (node (ref "LED5") (pin "2") (pinfunction "2_2") (pintype "passive"))
      (node (ref "M1") (pin "GND") (pinfunction "GND_GND") (pintype "passive"))
      (node (ref "Q4") (pin "E") (pinfunction "E_E") (pintype "passive"))
      (node (ref "R12") (pin "1") (pinfunction "1_1") (pintype "passive"))
      (node (ref "R13") (pin "2") (pinfunction "2_2") (pintype "passive"))
      (node (ref "R14") (pin "1") (pinfunction "1_1") (pintype "passive"))
      (node (ref "R15") (pin "1") (pinfunction "1_1") (pintype "passive"))
      (node (ref "R18") (pin "2") (pinfunction "2_2") (pintype "passive"))
      (node (ref "R19") (pin "1") (pinfunction "1_1") (pintype "passive"))
      (node (ref "R21") (pin "1") (pinfunction "1_1") (pintype "passive"))
      (node (ref "R22") (pin "1") (pinfunction "1_1") (pintype "passive"))
      (node (ref "R24") (pin "2") (pinfunction "2_2") (pintype "passive"))
      (node (ref "R29") (pin "2") (pinfunction "2_2") (pintype "passive"))
      (node (ref "R31") (pin "2") (pinfunction "2_2") (pintype "passive"))
      (node (ref "R35") (pin "2") (pinfunction "2_2") (pintype "passive"))
      (node (ref "R36") (pin "2") (pinfunction "2_2") (pintype "passive"))
      (node (ref "R37") (pin "2") (pinfunction "2_2") (pintype "passive"))
      (node (ref "R38") (pin "2") (pinfunction "2_2") (pintype "passive"))
      (node (ref "R41") (pin "2") (pinfunction "2_2") (pintype "passive"))
      (node (ref "SW1") (pin "1") (pinfunction "1_1") (pintype "passive"))
      (node (ref "SW2") (pin "2") (pinfunction "2_2") (pintype "passive"))
      (node (ref "U1") (pin "23") (pinfunction "VSS_1_23") (pintype "power_in"))
      (node (ref "U1") (pin "35") (pinfunction "VSS_2_35") (pintype "power_in"))
      (node (ref "U1") (pin "47") (pinfunction "VSS_3_47") (pintype "power_in"))
      (node (ref "U1") (pin "8") (pinfunction "VSSA_8") (pintype "power_in"))
      (node (ref "U2") (pin "1") (pinfunction "A0_1") (pintype "passive"))
      (node (ref "U2") (pin "2") (pinfunction "A1_2") (pintype "passive"))
      (node (ref "U2") (pin "3") (pinfunction "A2_3") (pintype "passive"))
      (node (ref "U2") (pin "4") (pinfunction "Gnd_4") (pintype "passive"))
      (node (ref "U2") (pin "7") (pinfunction "WP_7") (pintype "passive"))
      (node (ref "U3") (pin "2") (pinfunction "Gnd_2") (pintype "passive"))
      (node (ref "U4") (pin "GND") (pinfunction "GND_GND") (pintype "passive"))
      (node (ref "U4") (pin "GND_E") (pinfunction "GND_E_GND_E") (pintype "passive"))
      (node (ref "U5") (pin "GND") (pinfunction "Gnd_GND") (pintype "passive"))
      (node (ref "U6") (pin "GND") (pinfunction "Gnd_GND") (pintype "passive"))
      (node (ref "U7") (pin "GND") (pinfunction "Gnd_GND") (pintype "passive"))
    )
    (net (code "41") (name "Net-(C11-Pad1)") (class "Default")
      (node (ref "C11") (pin "1") (pinfunction "1_1") (pintype "passive"))
      (node (ref "U4") (pin "BST") (pinfunction "BST_BST") (pintype "passive"))
    )
    (net (code "42") (name "Net-(C11-Pad2)") (class "Default")
      (node (ref "C11") (pin "2") (pinfunction "2_2") (pintype "passive"))
      (node (ref "D2") (pin "K") (pinfunction "K_K") (pintype "passive"))
      (node (ref "L1") (pin "1") (pinfunction "1_1") (pintype "passive"))
      (node (ref "U4") (pin "SW") (pinfunction "SW_SW") (pintype "passive"))
    )
    (net (code "43") (name "Net-(C13-Pad1)") (class "Default")
      (node (ref "C13") (pin "1") (pinfunction "1_1") (pintype "passive"))
      (node (ref "R13") (pin "1") (pinfunction "1_1") (pintype "passive"))
    )
    (net (code "44") (name "Net-(C13-Pad2)") (class "Default")
      (node (ref "C13") (pin "2") (pinfunction "2_2") (pintype "passive"))
      (node (ref "U4") (pin "COMP") (pinfunction "COMP_COMP") (pintype "passive"))
    )
    (net (code "45") (name "Net-(D3-PadA)") (class "Default")
      (node (ref "D3") (pin "A") (pinfunction "A_A") (pintype "passive"))
      (node (ref "L2") (pin "2") (pinfunction "2_2") (pintype "passive"))
      (node (ref "U5") (pin "SW") (pinfunction "SW_SW") (pintype "passive"))
    )
    (net (code "46") (name "Net-(D4-PadA)") (class "Default")
      (node (ref "D4") (pin "A") (pinfunction "A_A") (pintype "passive"))
      (node (ref "L3") (pin "2") (pinfunction "2_2") (pintype "passive"))
      (node (ref "U7") (pin "SW") (pinfunction "SW_SW") (pintype "passive"))
    )
    (net (code "47") (name "Net-(F1-Pad1)") (class "Default")
      (node (ref "F1") (pin "1") (pinfunction "1_1") (pintype "passive"))
      (node (ref "J6") (pin "1") (pinfunction "1_1") (pintype "passive"))
    )
    (net (code "48") (name "Net-(J1-SWCLK)") (class "Default")
      (node (ref "J1") (pin "3") (pinfunction "SWCLK_3") (pintype "passive"))
      (node (ref "R38") (pin "1") (pinfunction "1_1") (pintype "passive"))
      (node (ref "U1") (pin "37") (pinfunction "PA14/JTCK/SWCLK_37") (pintype "bidirectional"))
    )
    (net (code "49") (name "Net-(J4-Vcc)") (class "Default")
      (node (ref "J4") (pin "1") (pinfunction "Vcc_1") (pintype "passive"))
      (node (ref "J5") (pin "2") (pinfunction "2_2") (pintype "passive"))
    )
    (net (code "50") (name "Net-(J7-Pad2)") (class "Default")
      (node (ref "J7") (pin "2") (pinfunction "2_2") (pintype "passive"))
      (node (ref "M1") (pin "RXD") (pinfunction "RXD_RXD") (pintype "passive"))
    )
    (net (code "51") (name "Net-(J8-Pad2)") (class "Default")
      (node (ref "J8") (pin "2") (pinfunction "2_2") (pintype "passive"))
      (node (ref "R25") (pin "1") (pinfunction "1_1") (pintype "passive"))
    )
    (net (code "52") (name "Net-(J9-12Vin)") (class "Default")
      (node (ref "F2") (pin "2") (pinfunction "2_2") (pintype "passive"))
      (node (ref "J9") (pin "1") (pinfunction "12Vin_1") (pintype "passive"))
    )
    (net (code "53") (name "Net-(J9-IO1)") (class "Default")
      (node (ref "J9") (pin "4") (pinfunction "IO1_4") (pintype "passive"))
      (node (ref "R27") (pin "2") (pinfunction "2_2") (pintype "passive"))
    )
    (net (code "54") (name "Net-(J9-IO2)") (class "Default")
      (node (ref "J9") (pin "5") (pinfunction "IO2_5") (pintype "passive"))
      (node (ref "R30") (pin "2") (pinfunction "2_2") (pintype "passive"))
    )
    (net (code "55") (name "Net-(J9-IO3)") (class "Default")
      (node (ref "J9") (pin "6") (pinfunction "IO3_6") (pintype "passive"))
      (node (ref "R34") (pin "2") (pinfunction "2_2") (pintype "passive"))
    )
    (net (code "56") (name "Net-(J9-IO4)") (class "Default")
      (node (ref "J9") (pin "7") (pinfunction "IO4_7") (pintype "passive"))
      (node (ref "R33") (pin "2") (pinfunction "2_2") (pintype "passive"))
    )
    (net (code "57") (name "Net-(J9-IO5)") (class "Default")
      (node (ref "J9") (pin "8") (pinfunction "IO5_8") (pintype "passive"))
      (node (ref "R32") (pin "2") (pinfunction "2_2") (pintype "passive"))
    )
    (net (code "58") (name "Net-(LED1-Pad1)") (class "Default")
      (node (ref "LED1") (pin "1") (pinfunction "1_1") (pintype "passive"))
      (node (ref "R6") (pin "2") (pinfunction "2_2") (pintype "passive"))
    )
    (net (code "59") (name "Net-(LED2-Pad1)") (class "Default")
      (node (ref "LED2") (pin "1") (pinfunction "1_1") (pintype "passive"))
      (node (ref "R7") (pin "2") (pinfunction "2_2") (pintype "passive"))
    )
    (net (code "60") (name "Net-(LED3-Pad1)") (class "Default")
      (node (ref "LED3") (pin "1") (pinfunction "1_1") (pintype "passive"))
      (node (ref "R9") (pin "1") (pinfunction "1_1") (pintype "passive"))
    )
    (net (code "61") (name "Net-(LED4-Pad2)") (class "Default")
      (node (ref "LED4") (pin "2") (pinfunction "2_2") (pintype "passive"))
      (node (ref "R17") (pin "1") (pinfunction "1_1") (pintype "passive"))
    )
    (net (code "62") (name "Net-(LED5-Pad1)") (class "Default")
      (node (ref "LED5") (pin "1") (pinfunction "1_1") (pintype "passive"))
      (node (ref "R40") (pin "1") (pinfunction "1_1") (pintype "passive"))
    )
    (net (code "63") (name "Net-(M1-PadTXD)") (class "Default")
      (node (ref "M1") (pin "TXD") (pinfunction "TXD_TXD") (pintype "passive"))
      (node (ref "R25") (pin "2") (pinfunction "2_2") (pintype "passive"))
    )
    (net (code "64") (name "Net-(Q1-PadG)") (class "Default")
      (node (ref "Q1") (pin "G") (pinfunction "G_G") (pintype "passive"))
      (node (ref "Q3") (pin "C") (pinfunction "C_C") (pintype "passive"))
      (node (ref "Q5") (pin "G") (pinfunction "G_G") (pintype "passive"))
      (node (ref "R21") (pin "2") (pinfunction "2_2") (pintype "passive"))
    )
    (net (code "65") (name "Net-(Q2-PadB)") (class "Default")
      (node (ref "Q2") (pin "B") (pinfunction "B_B") (pintype "passive"))
      (node (ref "Q2") (pin "C") (pinfunction "C_C") (pintype "passive"))
      (node (ref "Q3") (pin "B") (pinfunction "B_B") (pintype "passive"))
      (node (ref "R22") (pin "2") (pinfunction "2_2") (pintype "passive"))
    )
    (net (code "66") (name "Net-(Q4-PadB)") (class "Default")
      (node (ref "Q4") (pin "B") (pinfunction "B_B") (pintype "passive"))
      (node (ref "R23") (pin "1") (pinfunction "1_1") (pintype "passive"))
      (node (ref "R24") (pin "1") (pinfunction "1_1") (pintype "passive"))
    )
    (net (code "67") (name "Net-(R10-Pad2)") (class "Default")
      (node (ref "R10") (pin "2") (pinfunction "2_2") (pintype "passive"))
      (node (ref "R12") (pin "2") (pinfunction "2_2") (pintype "passive"))
      (node (ref "U4") (pin "EN") (pinfunction "EN_EN") (pintype "passive"))
    )
    (net (code "68") (name "Net-(R11-Pad2)") (class "Default")
      (node (ref "R11") (pin "2") (pinfunction "2_2") (pintype "passive"))
      (node (ref "R14") (pin "2") (pinfunction "2_2") (pintype "passive"))
      (node (ref "U4") (pin "FB") (pinfunction "FB_FB") (pintype "passive"))
    )
    (net (code "69") (name "Net-(R15-Pad2)") (class "Default")
      (node (ref "R15") (pin "2") (pinfunction "2_2") (pintype "passive"))
      (node (ref "U4") (pin "FREQ") (pinfunction "FREQ_FREQ") (pintype "passive"))
    )
    (net (code "70") (name "Net-(TP1-Antenna)") (class "Default")
      (node (ref "M1") (pin "ANT") (pinfunction "ANT_ANT") (pintype "passive"))
      (node (ref "TP1") (pin "1") (pinfunction "Antenna_1") (pintype "passive"))
    )
    (net (code "71") (name "Net-(U1-BOOT0)") (class "Default")
      (node (ref "J3") (pin "1") (pinfunction "1_1") (pintype "output"))
      (node (ref "U1") (pin "44") (pinfunction "BOOT0_44") (pintype "input"))
    )
    (net (code "72") (name "Net-(U1-OSC_IN{slash}PD0)") (class "Default")
      (node (ref "C4") (pin "2") (pinfunction "2_2") (pintype "passive"))
      (node (ref "U1") (pin "5") (pinfunction "OSC_IN/PD0_5") (pintype "input"))
      (node (ref "Xt1") (pin "1") (pinfunction "1_1") (pintype "output"))
    )
    (net (code "73") (name "Net-(U1-OSC_OUT{slash}PD1)") (class "Default")
      (node (ref "C5") (pin "2") (pinfunction "2_2") (pintype "passive"))
      (node (ref "U1") (pin "6") (pinfunction "OSC_OUT/PD1_6") (pintype "output"))
      (node (ref "Xt1") (pin "2") (pinfunction "2_2") (pintype "passive"))
    )
    (net (code "74") (name "Net-(U1-PA11{slash}USBDM)") (class "Default")
      (node (ref "C2") (pin "2") (pinfunction "2_2") (pintype "passive"))
      (node (ref "R5") (pin "1") (pinfunction "1_1") (pintype "passive"))
      (node (ref "U1") (pin "32") (pinfunction "PA11/USBDM_32") (pintype "bidirectional"))
    )
    (net (code "75") (name "Net-(U1-PA12{slash}USBDP)") (class "Default")
      (node (ref "C3") (pin "2") (pinfunction "2_2") (pintype "passive"))
      (node (ref "R3") (pin "1") (pinfunction "1_1") (pintype "passive"))
      (node (ref "R4") (pin "1") (pinfunction "1_1") (pintype "passive"))
      (node (ref "U1") (pin "33") (pinfunction "PA12/USBDP_33") (pintype "bidirectional"))
    )
    (net (code "76") (name "Net-(U1-PB6{slash}SCL1)") (class "Default")
      (node (ref "R2") (pin "1") (pinfunction "1_1") (pintype "passive"))
      (node (ref "U1") (pin "42") (pinfunction "PB6/SCL1_42") (pintype "bidirectional"))
      (node (ref "U2") (pin "6") (pinfunction "SCL_6") (pintype "passive"))
    )
    (net (code "77") (name "Net-(U1-PB7{slash}SDA1)") (class "Default")
      (node (ref "R1") (pin "1") (pinfunction "1_1") (pintype "passive"))
      (node (ref "U1") (pin "43") (pinfunction "PB7/SDA1_43") (pintype "bidirectional"))
      (node (ref "U2") (pin "5") (pinfunction "SDA_5") (pintype "passive"))
    )
    (net (code "78") (name "Net-(U1-PB10{slash}TX3)") (class "Default")
      (node (ref "J7") (pin "3") (pinfunction "3_3") (pintype "passive"))
      (node (ref "U1") (pin "21") (pinfunction "PB10/TX3_21") (pintype "bidirectional"))
    )
    (net (code "79") (name "Net-(U1-PB11{slash}RX3)") (class "Default")
      (node (ref "J8") (pin "3") (pinfunction "3_3") (pintype "passive"))
      (node (ref "U1") (pin "22") (pinfunction "PB11/RX3_22") (pintype "bidirectional"))
    )
    (net (code "80") (name "Net-(U5-En)") (class "Default")
      (node (ref "Q4") (pin "C") (pinfunction "C_C") (pintype "passive"))
      (node (ref "R20") (pin "2") (pinfunction "2_2") (pintype "passive"))
      (node (ref "U5") (pin "EN") (pinfunction "En_EN") (pintype "passive"))
      (node (ref "U7") (pin "EN") (pinfunction "En_EN") (pintype "passive"))
    )
    (net (code "81") (name "Net-(U6-Prog)") (class "Default")
      (node (ref "R18") (pin "1") (pinfunction "1_1") (pintype "passive"))
      (node (ref "U6") (pin "PROG") (pinfunction "Prog_PROG") (pintype "passive"))
    )
    (net (code "82") (name "Net-(U6-~{CHRG})") (class "Default")
      (node (ref "R17") (pin "2") (pinfunction "2_2") (pintype "passive"))
      (node (ref "U6") (pin "CHRG") (pinfunction "~{CHRG}_CHRG") (pintype "passive"))
    )
    (net (code "83") (name "Vbat") (class "Default")
      (node (ref "C15") (pin "+") (pinfunction "+_+") (pintype "passive"))
      (node (ref "C19") (pin "+") (pinfunction "+_+") (pintype "passive"))
      (node (ref "C21") (pin "1") (pinfunction "1_1") (pintype "passive"))
      (node (ref "C23") (pin "2") (pinfunction "2_2") (pintype "passive"))
      (node (ref "F1") (pin "2") (pinfunction "2_2") (pintype "passive"))
      (node (ref "L2") (pin "1") (pinfunction "1_1") (pintype "passive"))
      (node (ref "L3") (pin "1") (pinfunction "1_1") (pintype "passive"))
      (node (ref "M1") (pin "VCC") (pinfunction "VCC_VCC") (pintype "passive"))
      (node (ref "R20") (pin "1") (pinfunction "1_1") (pintype "passive"))
      (node (ref "U5") (pin "IN") (pinfunction "In_IN") (pintype "passive"))
      (node (ref "U6") (pin "BAT") (pinfunction "Bat_BAT") (pintype "passive"))
      (node (ref "U7") (pin "IN") (pinfunction "In_IN") (pintype "passive"))
    )
    (net (code "84") (name "unconnected-(HL1-Holder_Hole-Pad1)") (class "Default")
      (node (ref "HL1") (pin "1") (pinfunction "Holder_Hole_1") (pintype "passive"))
    )
    (net (code "85") (name "unconnected-(HL2-Holder_Hole-Pad1)") (class "Default")
      (node (ref "HL2") (pin "1") (pinfunction "Holder_Hole_1") (pintype "passive"))
    )
    (net (code "86") (name "unconnected-(J2-3.3V-Pad17)") (class "Default")
      (node (ref "J2") (pin "17") (pinfunction "3.3V_17") (pintype "passive+no_connect"))
    )
    (net (code "87") (name "unconnected-(M1-PadDTR)") (class "Default")
      (node (ref "M1") (pin "DTR") (pinfunction "DTR_DTR") (pintype "passive"))
    )
    (net (code "88") (name "unconnected-(M1-PadMIC+)") (class "Default")
      (node (ref "M1") (pin "MIC+") (pinfunction "MIC+_MIC+") (pintype "passive"))
    )
    (net (code "89") (name "unconnected-(M1-PadMIC-)") (class "Default")
      (node (ref "M1") (pin "MIC-") (pinfunction "MIC-_MIC-") (pintype "passive"))
    )
    (net (code "90") (name "unconnected-(M1-PadRING)") (class "Default")
      (node (ref "M1") (pin "RING") (pinfunction "RING_RING") (pintype "passive"))
    )
    (net (code "91") (name "unconnected-(M1-PadSPK+)") (class "Default")
      (node (ref "M1") (pin "SPK+") (pinfunction "SPK+_SPK+") (pintype "passive"))
    )
    (net (code "92") (name "unconnected-(M1-PadSPK-)") (class "Default")
      (node (ref "M1") (pin "SPK-") (pinfunction "SPK-_SPK-") (pintype "passive"))
    )
    (net (code "93") (name "unconnected-(U1-PA1-Pad11)") (class "Default")
      (node (ref "U1") (pin "11") (pinfunction "PA1_11") (pintype "bidirectional"))
    )
    (net (code "94") (name "unconnected-(U1-PA2-Pad12)") (class "Default")
      (node (ref "U1") (pin "12") (pinfunction "PA2_12") (pintype "bidirectional"))
    )
    (net (code "95") (name "unconnected-(U1-PA3-Pad13)") (class "Default")
      (node (ref "U1") (pin "13") (pinfunction "PA3_13") (pintype "bidirectional"))
    )
    (net (code "96") (name "unconnected-(U1-PA8-Pad29)") (class "Default")
      (node (ref "U1") (pin "29") (pinfunction "PA8_29") (pintype "bidirectional"))
    )
    (net (code "97") (name "unconnected-(U1-PA9-Pad30)") (class "Default")
      (node (ref "U1") (pin "30") (pinfunction "PA9_30") (pintype "bidirectional"))
    )
    (net (code "98") (name "unconnected-(U1-PA10-Pad31)") (class "Default")
      (node (ref "U1") (pin "31") (pinfunction "PA10_31") (pintype "bidirectional"))
    )
    (net (code "99") (name "unconnected-(U1-PA15{slash}JTDI-Pad38)") (class "Default")
      (node (ref "U1") (pin "38") (pinfunction "PA15/JTDI_38") (pintype "bidirectional"))
    )
    (net (code "100") (name "unconnected-(U1-PB1-Pad19)") (class "Default")
      (node (ref "U1") (pin "19") (pinfunction "PB1_19") (pintype "bidirectional"))
    )
    (net (code "101") (name "unconnected-(U1-PB3{slash}JTDO-Pad39)") (class "Default")
      (node (ref "U1") (pin "39") (pinfunction "PB3/JTDO_39") (pintype "bidirectional"))
    )
    (net (code "102") (name "unconnected-(U1-PB4{slash}JNTRST-Pad40)") (class "Default")
      (node (ref "U1") (pin "40") (pinfunction "PB4/JNTRST_40") (pintype "bidirectional"))
    )
    (net (code "103") (name "unconnected-(U1-PB5-Pad41)") (class "Default")
      (node (ref "U1") (pin "41") (pinfunction "PB5_41") (pintype "bidirectional"))
    )
    (net (code "104") (name "unconnected-(U1-PB8-Pad45)") (class "Default")
      (node (ref "U1") (pin "45") (pinfunction "PB8_45") (pintype "bidirectional"))
    )
    (net (code "105") (name "unconnected-(U1-PB9-Pad46)") (class "Default")
      (node (ref "U1") (pin "46") (pinfunction "PB9_46") (pintype "bidirectional"))
    )
    (net (code "106") (name "unconnected-(U1-PC13-TAMPER-RTC-Pad2)") (class "Default")
      (node (ref "U1") (pin "2") (pinfunction "PC13-TAMPER-RTC_2") (pintype "bidirectional"))
    )
    (net (code "107") (name "unconnected-(U1-VBAT-Pad1)") (class "Default")
      (node (ref "U1") (pin "1") (pinfunction "VBAT_1") (pintype "power_in"))
    )
    (net (code "108") (name "unconnected-(U5-PadNC)") (class "Default")
      (node (ref "U5") (pin "NC") (pinfunction "NC_NC") (pintype "passive+no_connect"))
    )
    (net (code "109") (name "unconnected-(U7-PadNC)") (class "Default")
      (node (ref "U7") (pin "NC") (pinfunction "NC_NC") (pintype "passive+no_connect"))
    )
  )
)
